# SCH_Czujnik-Wody_2026-02-04.net
KiCad netlist of a schematic drawn in EasyEDA
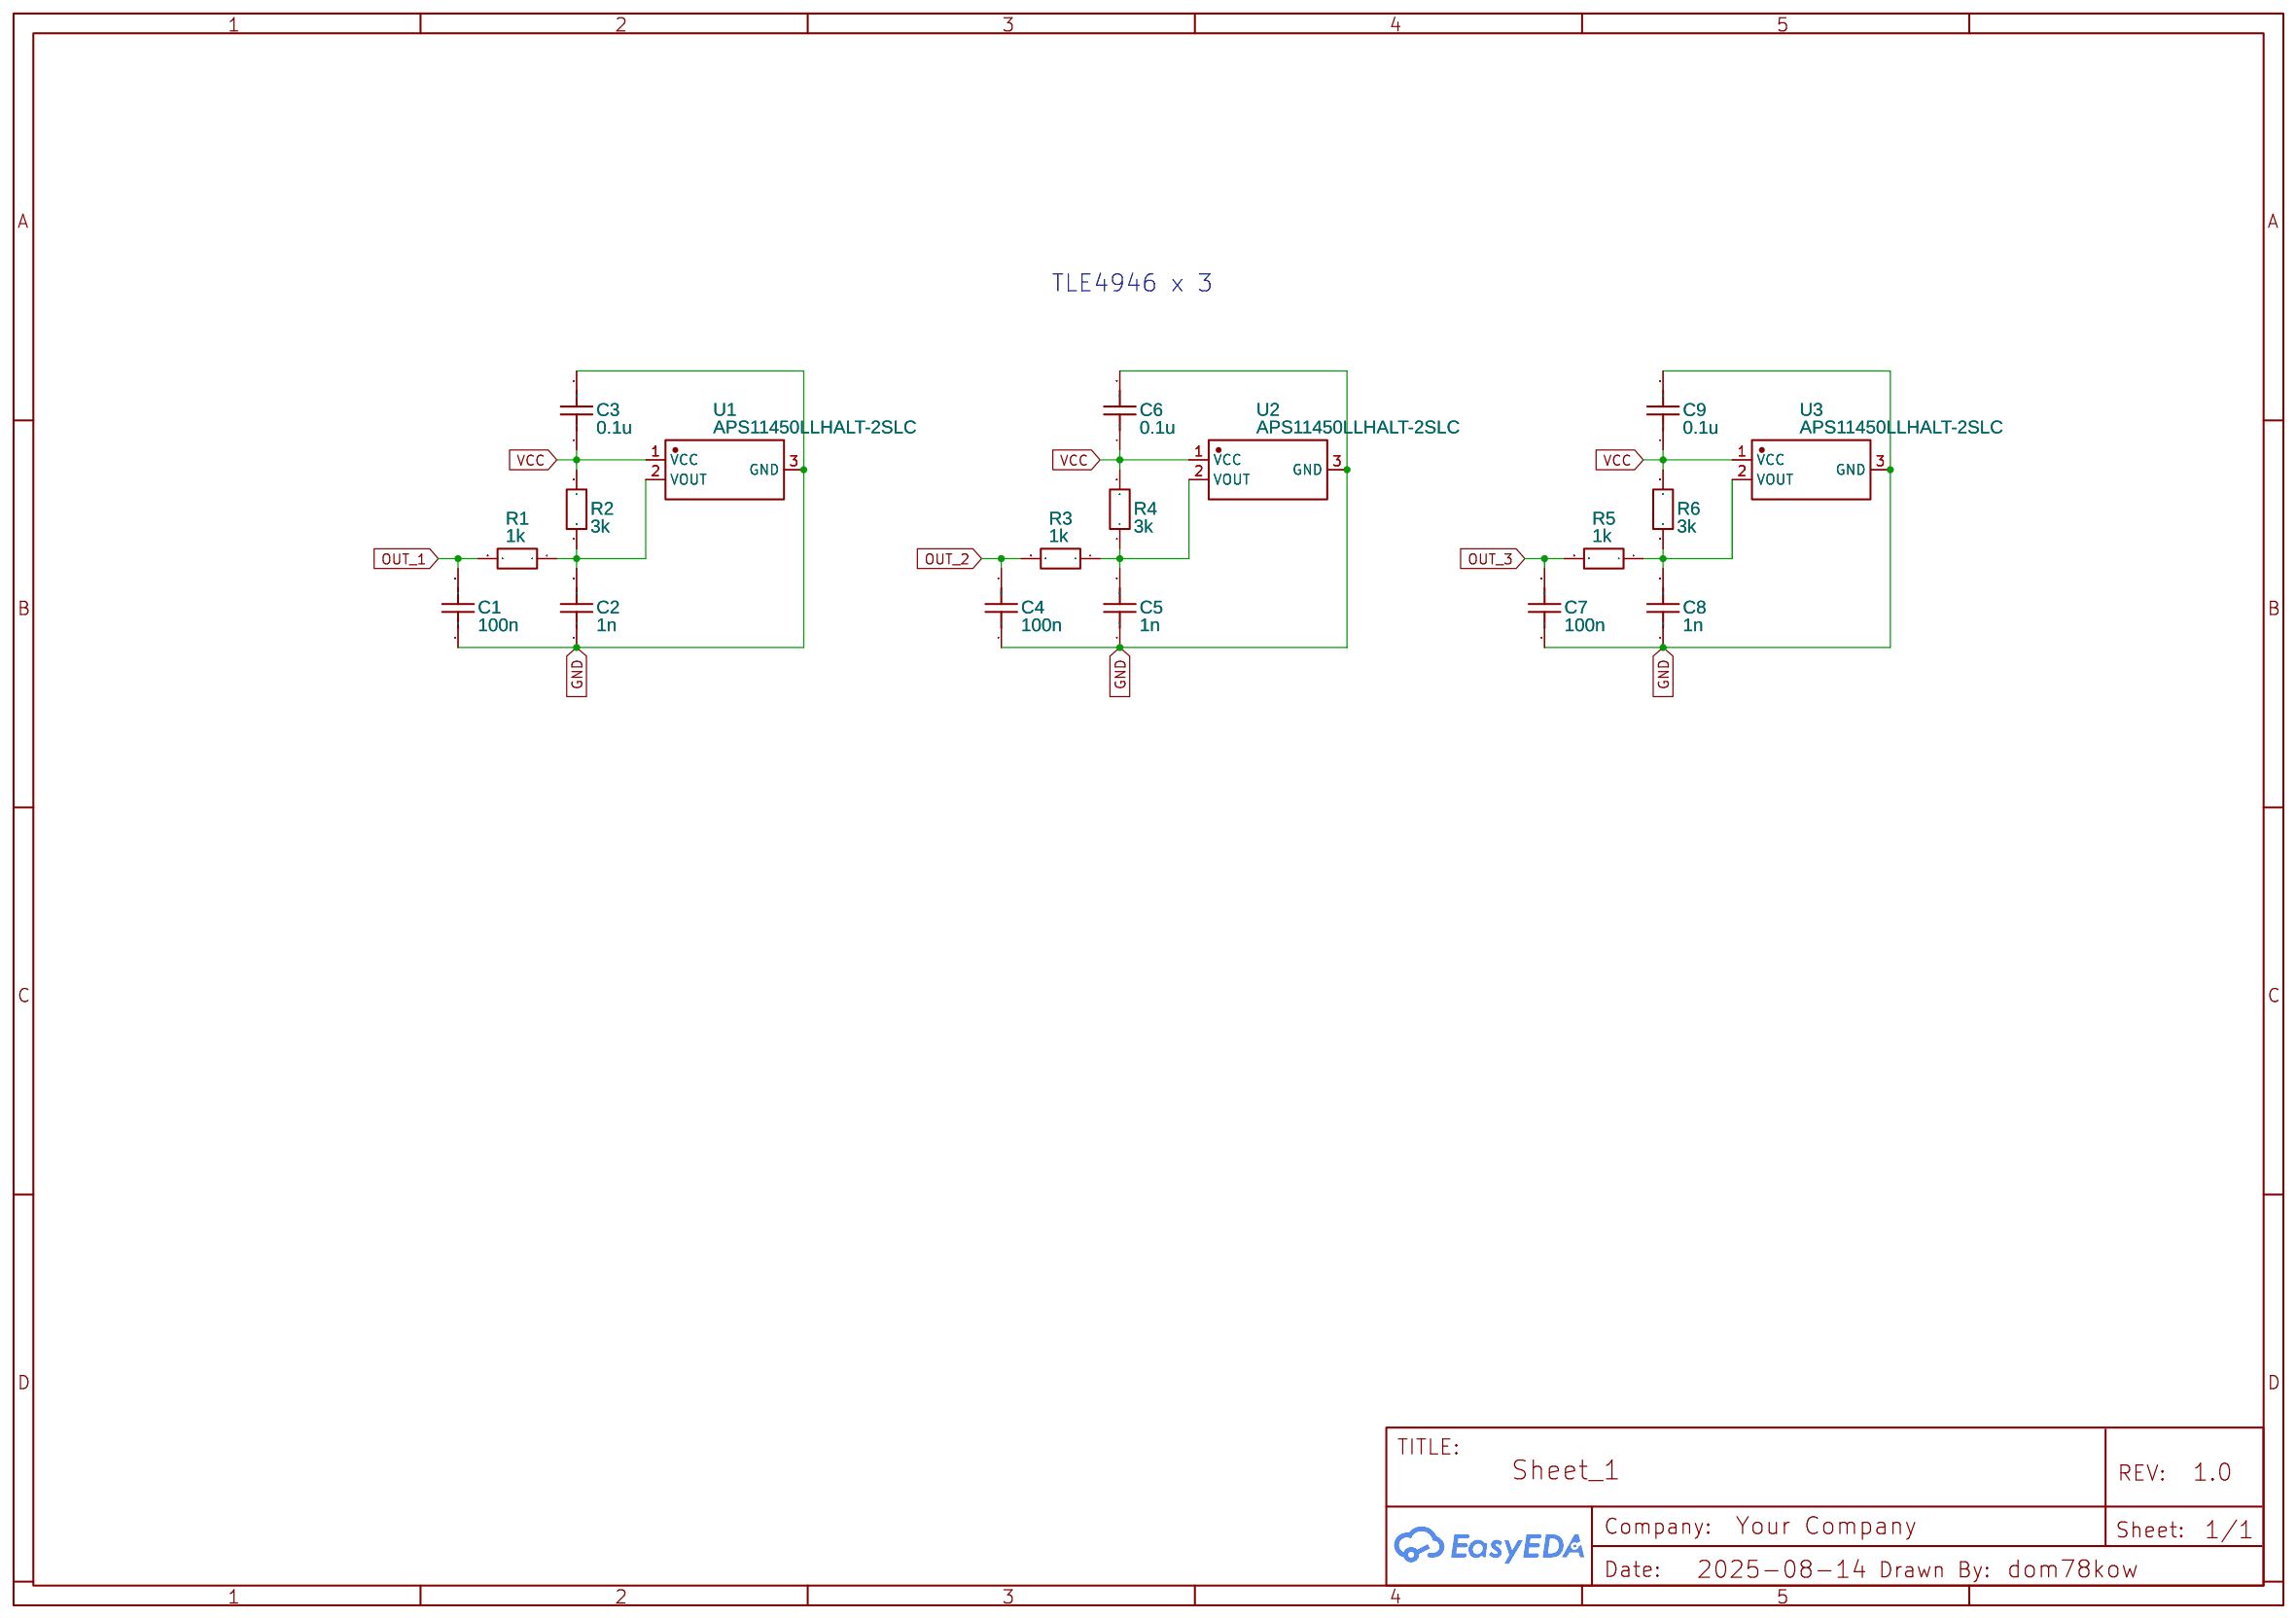
[diagram p0: schematic sheet]

(export (version "E")
  (design (tool "Eeschema 10.0.6"))
  (components
    (comp (ref "C1") (value "100n") (libsource (lib "") (part "C_0805_US")))
    (comp (ref "C2") (value "1n") (libsource (lib "") (part "C_0805_US")))
    (comp (ref "C3") (value "0.1u") (libsource (lib "") (part "C_0805_US")))
    (comp (ref "C4") (value "100n") (libsource (lib "") (part "C_0805_US")))
    (comp (ref "C5") (value "1n") (libsource (lib "") (part "C_0805_US")))
    (comp (ref "C6") (value "0.1u") (libsource (lib "") (part "C_0805_US")))
    (comp (ref "C7") (value "100n") (libsource (lib "") (part "C_0805_US")))
    (comp (ref "C8") (value "1n") (libsource (lib "") (part "C_0805_US")))
    (comp (ref "C9") (value "0.1u") (libsource (lib "") (part "C_0805_US")))
    (comp (ref "R1") (value "1k") (libsource (lib "") (part "R_0805_EU_1")))
    (comp (ref "R2") (value "3k") (libsource (lib "") (part "R_0805_EU")))
    (comp (ref "R3") (value "1k") (libsource (lib "") (part "R_0805_EU_1")))
    (comp (ref "R4") (value "3k") (libsource (lib "") (part "R_0805_EU")))
    (comp (ref "R5") (value "1k") (libsource (lib "") (part "R_0805_EU_1")))
    (comp (ref "R6") (value "3k") (libsource (lib "") (part "R_0805_EU")))
    (comp (ref "U1")
      (value "APS11450LLHALT-2SLC")
      (fields (field (name "Manufacturer") "ALLEGRO(美国埃戈罗)"))
      (libsource (lib "") (part "APS11450LLHALT-2SLC"))
    )
    (comp (ref "U2")
      (value "APS11450LLHALT-2SLC")
      (fields (field (name "Manufacturer") "ALLEGRO(美国埃戈罗)"))
      (libsource (lib "") (part "APS11450LLHALT-2SLC"))
    )
    (comp (ref "U3")
      (value "APS11450LLHALT-2SLC")
      (fields (field (name "Manufacturer") "ALLEGRO(美国埃戈罗)"))
      (libsource (lib "") (part "APS11450LLHALT-2SLC"))
    )
  )
  (nets
    (net (code "1") (name "GND") (class "Default")
      (node (ref "C1") (pin "1") (pinfunction "1_1") (pintype "unspecified"))
      (node (ref "C2") (pin "1") (pinfunction "1_1") (pintype "unspecified"))
      (node (ref "C3") (pin "2") (pinfunction "2_2") (pintype "unspecified"))
      (node (ref "C4") (pin "1") (pinfunction "1_1") (pintype "unspecified"))
      (node (ref "C5") (pin "1") (pinfunction "1_1") (pintype "unspecified"))
      (node (ref "C6") (pin "2") (pinfunction "2_2") (pintype "unspecified"))
      (node (ref "C7") (pin "1") (pinfunction "1_1") (pintype "unspecified"))
      (node (ref "C8") (pin "1") (pinfunction "1_1") (pintype "unspecified"))
      (node (ref "C9") (pin "2") (pinfunction "2_2") (pintype "unspecified"))
      (node (ref "U1") (pin "3") (pinfunction "GND_3") (pintype "unspecified"))
      (node (ref "U2") (pin "3") (pinfunction "GND_3") (pintype "unspecified"))
      (node (ref "U3") (pin "3") (pinfunction "GND_3") (pintype "unspecified"))
    )
    (net (code "2") (name "Net-(U1-VOUT)") (class "Default")
      (node (ref "C2") (pin "2") (pinfunction "2_2") (pintype "unspecified"))
      (node (ref "R1") (pin "1") (pinfunction "1_1") (pintype "unspecified"))
      (node (ref "R2") (pin "1") (pinfunction "1_1") (pintype "unspecified"))
      (node (ref "U1") (pin "2") (pinfunction "VOUT_2") (pintype "unspecified"))
    )
    (net (code "3") (name "Net-(U2-VOUT)") (class "Default")
      (node (ref "C5") (pin "2") (pinfunction "2_2") (pintype "unspecified"))
      (node (ref "R3") (pin "1") (pinfunction "1_1") (pintype "unspecified"))
      (node (ref "R4") (pin "1") (pinfunction "1_1") (pintype "unspecified"))
      (node (ref "U2") (pin "2") (pinfunction "VOUT_2") (pintype "unspecified"))
    )
    (net (code "4") (name "Net-(U3-VOUT)") (class "Default")
      (node (ref "C8") (pin "2") (pinfunction "2_2") (pintype "unspecified"))
      (node (ref "R5") (pin "1") (pinfunction "1_1") (pintype "unspecified"))
      (node (ref "R6") (pin "1") (pinfunction "1_1") (pintype "unspecified"))
      (node (ref "U3") (pin "2") (pinfunction "VOUT_2") (pintype "unspecified"))
    )
    (net (code "5") (name "OUT_1") (class "Default")
      (node (ref "C1") (pin "2") (pinfunction "2_2") (pintype "unspecified"))
      (node (ref "R1") (pin "2") (pinfunction "2_2") (pintype "unspecified"))
    )
    (net (code "6") (name "OUT_2") (class "Default")
      (node (ref "C4") (pin "2") (pinfunction "2_2") (pintype "unspecified"))
      (node (ref "R3") (pin "2") (pinfunction "2_2") (pintype "unspecified"))
    )
    (net (code "7") (name "OUT_3") (class "Default")
      (node (ref "C7") (pin "2") (pinfunction "2_2") (pintype "unspecified"))
      (node (ref "R5") (pin "2") (pinfunction "2_2") (pintype "unspecified"))
    )
    (net (code "8") (name "VCC") (class "Default")
      (node (ref "C3") (pin "1") (pinfunction "1_1") (pintype "unspecified"))
      (node (ref "C6") (pin "1") (pinfunction "1_1") (pintype "unspecified"))
      (node (ref "C9") (pin "1") (pinfunction "1_1") (pintype "unspecified"))
      (node (ref "R2") (pin "2") (pinfunction "2_2") (pintype "unspecified"))
      (node (ref "R4") (pin "2") (pinfunction "2_2") (pintype "unspecified"))
      (node (ref "R6") (pin "2") (pinfunction "2_2") (pintype "unspecified"))
      (node (ref "U1") (pin "1") (pinfunction "VCC_1") (pintype "unspecified"))
      (node (ref "U2") (pin "1") (pinfunction "VCC_1") (pintype "unspecified"))
      (node (ref "U3") (pin "1") (pinfunction "VCC_1") (pintype "unspecified"))
    )
  )
)
